# Multivibrator.net
KiCad netlist of a schematic drawn in Altium Designer
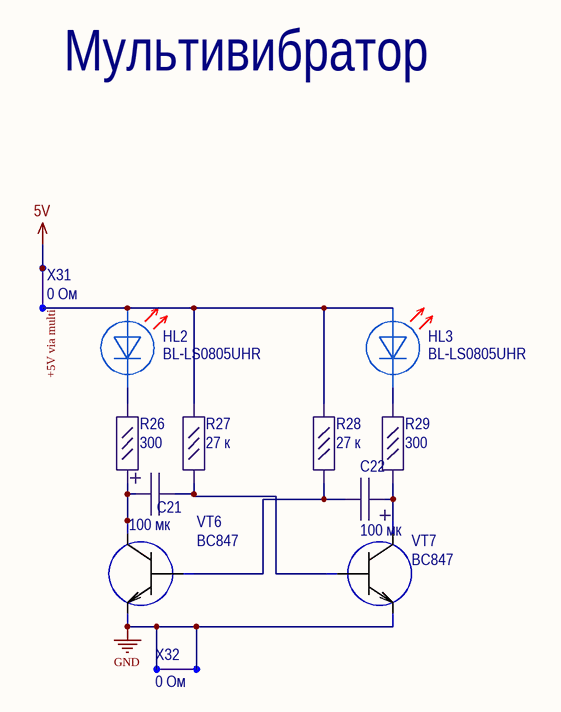
[diagram p0: Multivibrator.SchDoc]

(export (version "E")
  (design (tool "Eeschema 10.0.6"))
  (components
    (comp (ref "C21")
      (value "100 мк")
      (footprint "User_Library:SMD_al_cap_0605_6.3")
      (description "CAP TANT 100UF 10% 4V 1411")
      (fields (field (name "PART NUMBER") "TAJB107K004RNJ") (field (name "MANUFACTURER") "AVX Corporation"))
      (libsource (lib "Database_Lib") (part "Tantalum Capacitor"))
    )
    (comp (ref "C22")
      (value "100 мк")
      (footprint "User_Library:SMD_al_cap_0605_6.3")
      (description "CAP TANT 100UF 10% 4V 1411")
      (fields (field (name "PART NUMBER") "TAJB107K004RNJ") (field (name "MANUFACTURER") "AVX Corporation"))
      (libsource (lib "Database_Lib") (part "Tantalum Capacitor"))
    )
    (comp (ref "HL2")
      (value "BL-LS0805UHR")
      (footprint "PCB2:LED_0805_RED")
      (libsource (lib "4.Diodes") (part "BL-LS0805UHR"))
    )
    (comp (ref "HL3")
      (value "BL-LS0805UHR")
      (footprint "PCB2:LED_0805_RED")
      (libsource (lib "4.Diodes") (part "BL-LS0805UHR"))
    )
    (comp (ref "R26")
      (value "300")
      (footprint "1.Resistors:R_0805")
      (description "RES SMD 10K OHM 1% 1/10W 0603")
      (fields (field (name "PART NUMBER") "CR0603-FX-1002ELF") (field (name "MANUFACTURER") "Bourns Inc."))
      (libsource (lib "Database_Lib") (part "Resistor"))
    )
    (comp (ref "R27")
      (value "27 к")
      (footprint "1.Resistors:R_0805")
      (description "RES SMD 10K OHM 1% 1/10W 0603")
      (fields (field (name "PART NUMBER") "CR0603-FX-1002ELF") (field (name "MANUFACTURER") "Bourns Inc."))
      (libsource (lib "Database_Lib") (part "Resistor"))
    )
    (comp (ref "R28")
      (value "27 к")
      (footprint "1.Resistors:R_0805")
      (description "RES SMD 10K OHM 1% 1/10W 0603")
      (fields (field (name "PART NUMBER") "CR0603-FX-1002ELF") (field (name "MANUFACTURER") "Bourns Inc."))
      (libsource (lib "Database_Lib") (part "Resistor"))
    )
    (comp (ref "R29")
      (value "300")
      (footprint "1.Resistors:R_0805")
      (description "RES SMD 10K OHM 1% 1/10W 0603")
      (fields (field (name "PART NUMBER") "CR0603-FX-1002ELF") (field (name "MANUFACTURER") "Bourns Inc."))
      (libsource (lib "Database_Lib") (part "Resistor"))
    )
    (comp (ref "VT6") (value "BC847") (footprint "SOT23") (libsource (lib "5.Transistors") (part "BC847")))
    (comp (ref "VT7") (value "BC847") (footprint "SOT23") (libsource (lib "5.Transistors") (part "BC847")))
    (comp (ref "X31")
      (value "0 Ом")
      (footprint "7.Connectors&Battary_holders:PLS-2")
      (libsource (lib "11.Other") (part "0 Ohm (0805)"))
    )
    (comp (ref "X32")
      (value "0 Ом")
      (footprint "7.Connectors&Battary_holders:PLS-2")
      (libsource (lib "11.Other") (part "0 Ohm (0805)"))
    )
  )
  (nets
    (net (code "1") (name "/+5V via multi") (class "Default")
      (node (ref "HL2") (pin "1") (pinfunction "1_1") (pintype "passive"))
      (node (ref "HL3") (pin "1") (pinfunction "1_1") (pintype "passive"))
      (node (ref "R27") (pin "1") (pinfunction "1_1") (pintype "passive"))
      (node (ref "R28") (pin "1") (pinfunction "1_1") (pintype "passive"))
      (node (ref "X31") (pin "1") (pinfunction "1_1") (pintype "passive"))
    )
    (net (code "2") (name "5V") (class "Default")
      (node (ref "X31") (pin "2") (pinfunction "2_2") (pintype "passive"))
    )
    (net (code "3") (name "GND") (class "Default")
      (node (ref "VT6") (pin "2") (pinfunction "E_2") (pintype "passive"))
      (node (ref "VT7") (pin "2") (pinfunction "E_2") (pintype "passive"))
      (node (ref "X32") (pin "1") (pinfunction "1_1") (pintype "passive"))
      (node (ref "X32") (pin "2") (pinfunction "2_2") (pintype "passive"))
    )
    (net (code "4") (name "Net-(HL2-Pad2)") (class "Default")
      (node (ref "HL2") (pin "2") (pinfunction "2_2") (pintype "passive"))
      (node (ref "R26") (pin "1") (pinfunction "1_1") (pintype "passive"))
    )
    (net (code "5") (name "Net-(HL3-Pad2)") (class "Default")
      (node (ref "HL3") (pin "2") (pinfunction "2_2") (pintype "passive"))
      (node (ref "R29") (pin "1") (pinfunction "1_1") (pintype "passive"))
    )
    (net (code "6") (name "Net-(VT6-B)") (class "Default")
      (node (ref "C22") (pin "2") (pinfunction "2_2") (pintype "passive"))
      (node (ref "R28") (pin "2") (pinfunction "2_2") (pintype "passive"))
      (node (ref "VT6") (pin "1") (pinfunction "B_1") (pintype "passive"))
    )
    (net (code "7") (name "Net-(VT6-C)") (class "Default")
      (node (ref "C21") (pin "1") (pinfunction "1_1") (pintype "passive"))
      (node (ref "R26") (pin "2") (pinfunction "2_2") (pintype "passive"))
      (node (ref "VT6") (pin "3") (pinfunction "C_3") (pintype "passive"))
    )
    (net (code "8") (name "Net-(VT7-B)") (class "Default")
      (node (ref "C21") (pin "2") (pinfunction "2_2") (pintype "passive"))
      (node (ref "R27") (pin "2") (pinfunction "2_2") (pintype "passive"))
      (node (ref "VT7") (pin "1") (pinfunction "B_1") (pintype "passive"))
    )
    (net (code "9") (name "Net-(VT7-C)") (class "Default")
      (node (ref "C22") (pin "1") (pinfunction "1_1") (pintype "passive"))
      (node (ref "R29") (pin "2") (pinfunction "2_2") (pintype "passive"))
      (node (ref "VT7") (pin "3") (pinfunction "C_3") (pintype "passive"))
    )
  )
)
